# uSD_test_board.net
KiCad netlist of a schematic drawn in EAGLE
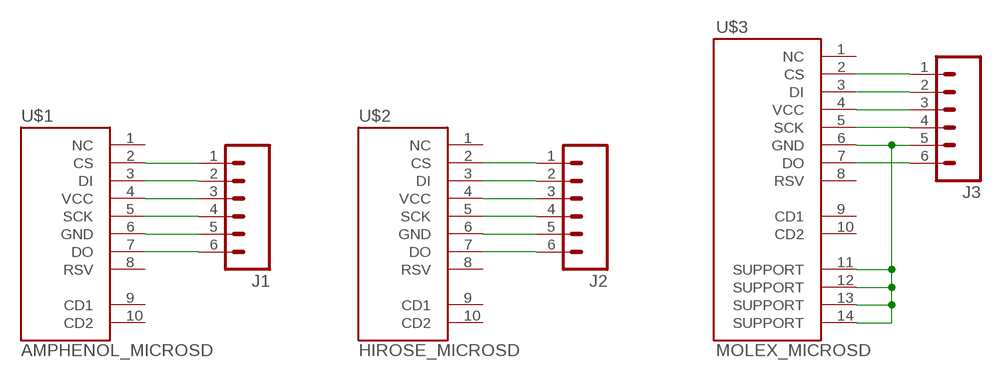
[diagram p0: schematic, sheet 1]

(export (version "E")
  (design (tool "Eeschema 10.0.6"))
  (components
    (comp (ref "J1")
      (value "M06SILK_FEMALE_PTH")
      (footprint "eagle-import:1X06")
      (libsource (lib "eagle-import") (part "M06SILK_FEMALE_PTH"))
    )
    (comp (ref "J2")
      (value "M06SILK_FEMALE_PTH")
      (footprint "eagle-import:1X06")
      (libsource (lib "eagle-import") (part "M06SILK_FEMALE_PTH"))
    )
    (comp (ref "J3")
      (value "M06SILK_FEMALE_PTH")
      (footprint "eagle-import:1X06")
      (libsource (lib "eagle-import") (part "M06SILK_FEMALE_PTH"))
    )
    (comp (ref "U$1")
      (value "AMPHENOL_MICROSD")
      (footprint "eagle-import:AMPHENOL_MICROSD")
      (libsource (lib "eagle-import") (part "AMPHENOL_MICROSD"))
    )
    (comp (ref "U$2")
      (value "HIROSE_MICROSD")
      (footprint "eagle-import:AMPHENOL_MICROSD")
      (libsource (lib "eagle-import") (part "HIROSE_MICROSD"))
    )
    (comp (ref "U$3")
      (value "MOLEX_MICROSD")
      (footprint "eagle-import:MOLEX_MICROSD")
      (libsource (lib "eagle-import") (part "MOLEX_MICROSD"))
    )
  )
  (nets
    (net (code "1") (name "/GND") (class "Default")
      (node (ref "J1") (pin "5") (pinfunction "5_5") (pintype "passive"))
      (node (ref "J2") (pin "5") (pinfunction "5_5") (pintype "passive"))
      (node (ref "J3") (pin "5") (pinfunction "5_5") (pintype "passive"))
      (node (ref "U$1") (pin "6") (pinfunction "GND_6") (pintype "power_in"))
      (node (ref "U$2") (pin "6") (pinfunction "GND_6") (pintype "power_in"))
      (node (ref "U$3") (pin "11") (pinfunction "SUPPORT_11") (pintype "power_in"))
      (node (ref "U$3") (pin "12") (pinfunction "SUPPORT_12") (pintype "power_in"))
      (node (ref "U$3") (pin "13") (pinfunction "SUPPORT_13") (pintype "power_in"))
      (node (ref "U$3") (pin "14") (pinfunction "SUPPORT_14") (pintype "power_in"))
      (node (ref "U$3") (pin "6") (pinfunction "GND_6") (pintype "power_in"))
    )
    (net (code "2") (name "Net-(U$1-CS)") (class "Default")
      (node (ref "J1") (pin "1") (pinfunction "1_1") (pintype "passive"))
      (node (ref "U$1") (pin "2") (pinfunction "CS_2") (pintype "input"))
    )
    (net (code "3") (name "Net-(U$1-DI)") (class "Default")
      (node (ref "J1") (pin "2") (pinfunction "2_2") (pintype "passive"))
      (node (ref "U$1") (pin "3") (pinfunction "DI_3") (pintype "input"))
    )
    (net (code "4") (name "Net-(U$1-DO)") (class "Default")
      (node (ref "J1") (pin "6") (pinfunction "6_6") (pintype "passive"))
      (node (ref "U$1") (pin "7") (pinfunction "DO_7") (pintype "output"))
    )
    (net (code "5") (name "Net-(U$1-SCK)") (class "Default")
      (node (ref "J1") (pin "4") (pinfunction "4_4") (pintype "passive"))
      (node (ref "U$1") (pin "5") (pinfunction "SCK_5") (pintype "bidirectional"))
    )
    (net (code "6") (name "Net-(U$1-VCC)") (class "Default")
      (node (ref "J1") (pin "3") (pinfunction "3_3") (pintype "passive"))
      (node (ref "U$1") (pin "4") (pinfunction "VCC_4") (pintype "power_in"))
    )
    (net (code "7") (name "Net-(U$2-CS)") (class "Default")
      (node (ref "J2") (pin "1") (pinfunction "1_1") (pintype "passive"))
      (node (ref "U$2") (pin "2") (pinfunction "CS_2") (pintype "input"))
    )
    (net (code "8") (name "Net-(U$2-DI)") (class "Default")
      (node (ref "J2") (pin "2") (pinfunction "2_2") (pintype "passive"))
      (node (ref "U$2") (pin "3") (pinfunction "DI_3") (pintype "input"))
    )
    (net (code "9") (name "Net-(U$2-DO)") (class "Default")
      (node (ref "J2") (pin "6") (pinfunction "6_6") (pintype "passive"))
      (node (ref "U$2") (pin "7") (pinfunction "DO_7") (pintype "output"))
    )
    (net (code "10") (name "Net-(U$2-SCK)") (class "Default")
      (node (ref "J2") (pin "4") (pinfunction "4_4") (pintype "passive"))
      (node (ref "U$2") (pin "5") (pinfunction "SCK_5") (pintype "bidirectional"))
    )
    (net (code "11") (name "Net-(U$2-VCC)") (class "Default")
      (node (ref "J2") (pin "3") (pinfunction "3_3") (pintype "passive"))
      (node (ref "U$2") (pin "4") (pinfunction "VCC_4") (pintype "power_in"))
    )
    (net (code "12") (name "Net-(U$3-CS)") (class "Default")
      (node (ref "J3") (pin "1") (pinfunction "1_1") (pintype "passive"))
      (node (ref "U$3") (pin "2") (pinfunction "CS_2") (pintype "input"))
    )
    (net (code "13") (name "Net-(U$3-DI)") (class "Default")
      (node (ref "J3") (pin "2") (pinfunction "2_2") (pintype "passive"))
      (node (ref "U$3") (pin "3") (pinfunction "DI_3") (pintype "input"))
    )
    (net (code "14") (name "Net-(U$3-DO)") (class "Default")
      (node (ref "J3") (pin "6") (pinfunction "6_6") (pintype "passive"))
      (node (ref "U$3") (pin "7") (pinfunction "DO_7") (pintype "output"))
    )
    (net (code "15") (name "Net-(U$3-SCK)") (class "Default")
      (node (ref "J3") (pin "4") (pinfunction "4_4") (pintype "passive"))
      (node (ref "U$3") (pin "5") (pinfunction "SCK_5") (pintype "bidirectional"))
    )
    (net (code "16") (name "Net-(U$3-VCC)") (class "Default")
      (node (ref "J3") (pin "3") (pinfunction "3_3") (pintype "passive"))
      (node (ref "U$3") (pin "4") (pinfunction "VCC_4") (pintype "power_in"))
    )
    (net (code "17") (name "unconnected-(U$1-CD1-Pad9)") (class "Default")
      (node (ref "U$1") (pin "9") (pinfunction "CD1_9") (pintype "bidirectional"))
    )
    (net (code "18") (name "unconnected-(U$1-CD2-Pad10)") (class "Default")
      (node (ref "U$1") (pin "10") (pinfunction "CD2_10") (pintype "bidirectional"))
    )
    (net (code "19") (name "unconnected-(U$1-NC-Pad1)") (class "Default")
      (node (ref "U$1") (pin "1") (pinfunction "NC_1") (pintype "no_connect"))
    )
    (net (code "20") (name "unconnected-(U$1-RSV-Pad8)") (class "Default")
      (node (ref "U$1") (pin "8") (pinfunction "RSV_8") (pintype "bidirectional"))
    )
    (net (code "21") (name "unconnected-(U$2-CD1-Pad9)") (class "Default")
      (node (ref "U$2") (pin "9") (pinfunction "CD1_9") (pintype "bidirectional"))
    )
    (net (code "22") (name "unconnected-(U$2-CD2-Pad10)") (class "Default")
      (node (ref "U$2") (pin "10") (pinfunction "CD2_10") (pintype "bidirectional"))
    )
    (net (code "23") (name "unconnected-(U$2-NC-Pad1)") (class "Default")
      (node (ref "U$2") (pin "1") (pinfunction "NC_1") (pintype "no_connect"))
    )
    (net (code "24") (name "unconnected-(U$2-RSV-Pad8)") (class "Default")
      (node (ref "U$2") (pin "8") (pinfunction "RSV_8") (pintype "bidirectional"))
    )
    (net (code "25") (name "unconnected-(U$3-CD1-Pad9)") (class "Default")
      (node (ref "U$3") (pin "9") (pinfunction "CD1_9") (pintype "bidirectional"))
    )
    (net (code "26") (name "unconnected-(U$3-CD2-Pad10)") (class "Default")
      (node (ref "U$3") (pin "10") (pinfunction "CD2_10") (pintype "bidirectional"))
    )
    (net (code "27") (name "unconnected-(U$3-NC-Pad1)") (class "Default")
      (node (ref "U$3") (pin "1") (pinfunction "NC_1") (pintype "no_connect"))
    )
    (net (code "28") (name "unconnected-(U$3-RSV-Pad8)") (class "Default")
      (node (ref "U$3") (pin "8") (pinfunction "RSV_8") (pintype "bidirectional"))
    )
  )
)
